# Precision_ATMega32U4.net
KiCad netlist of a schematic drawn in EAGLE
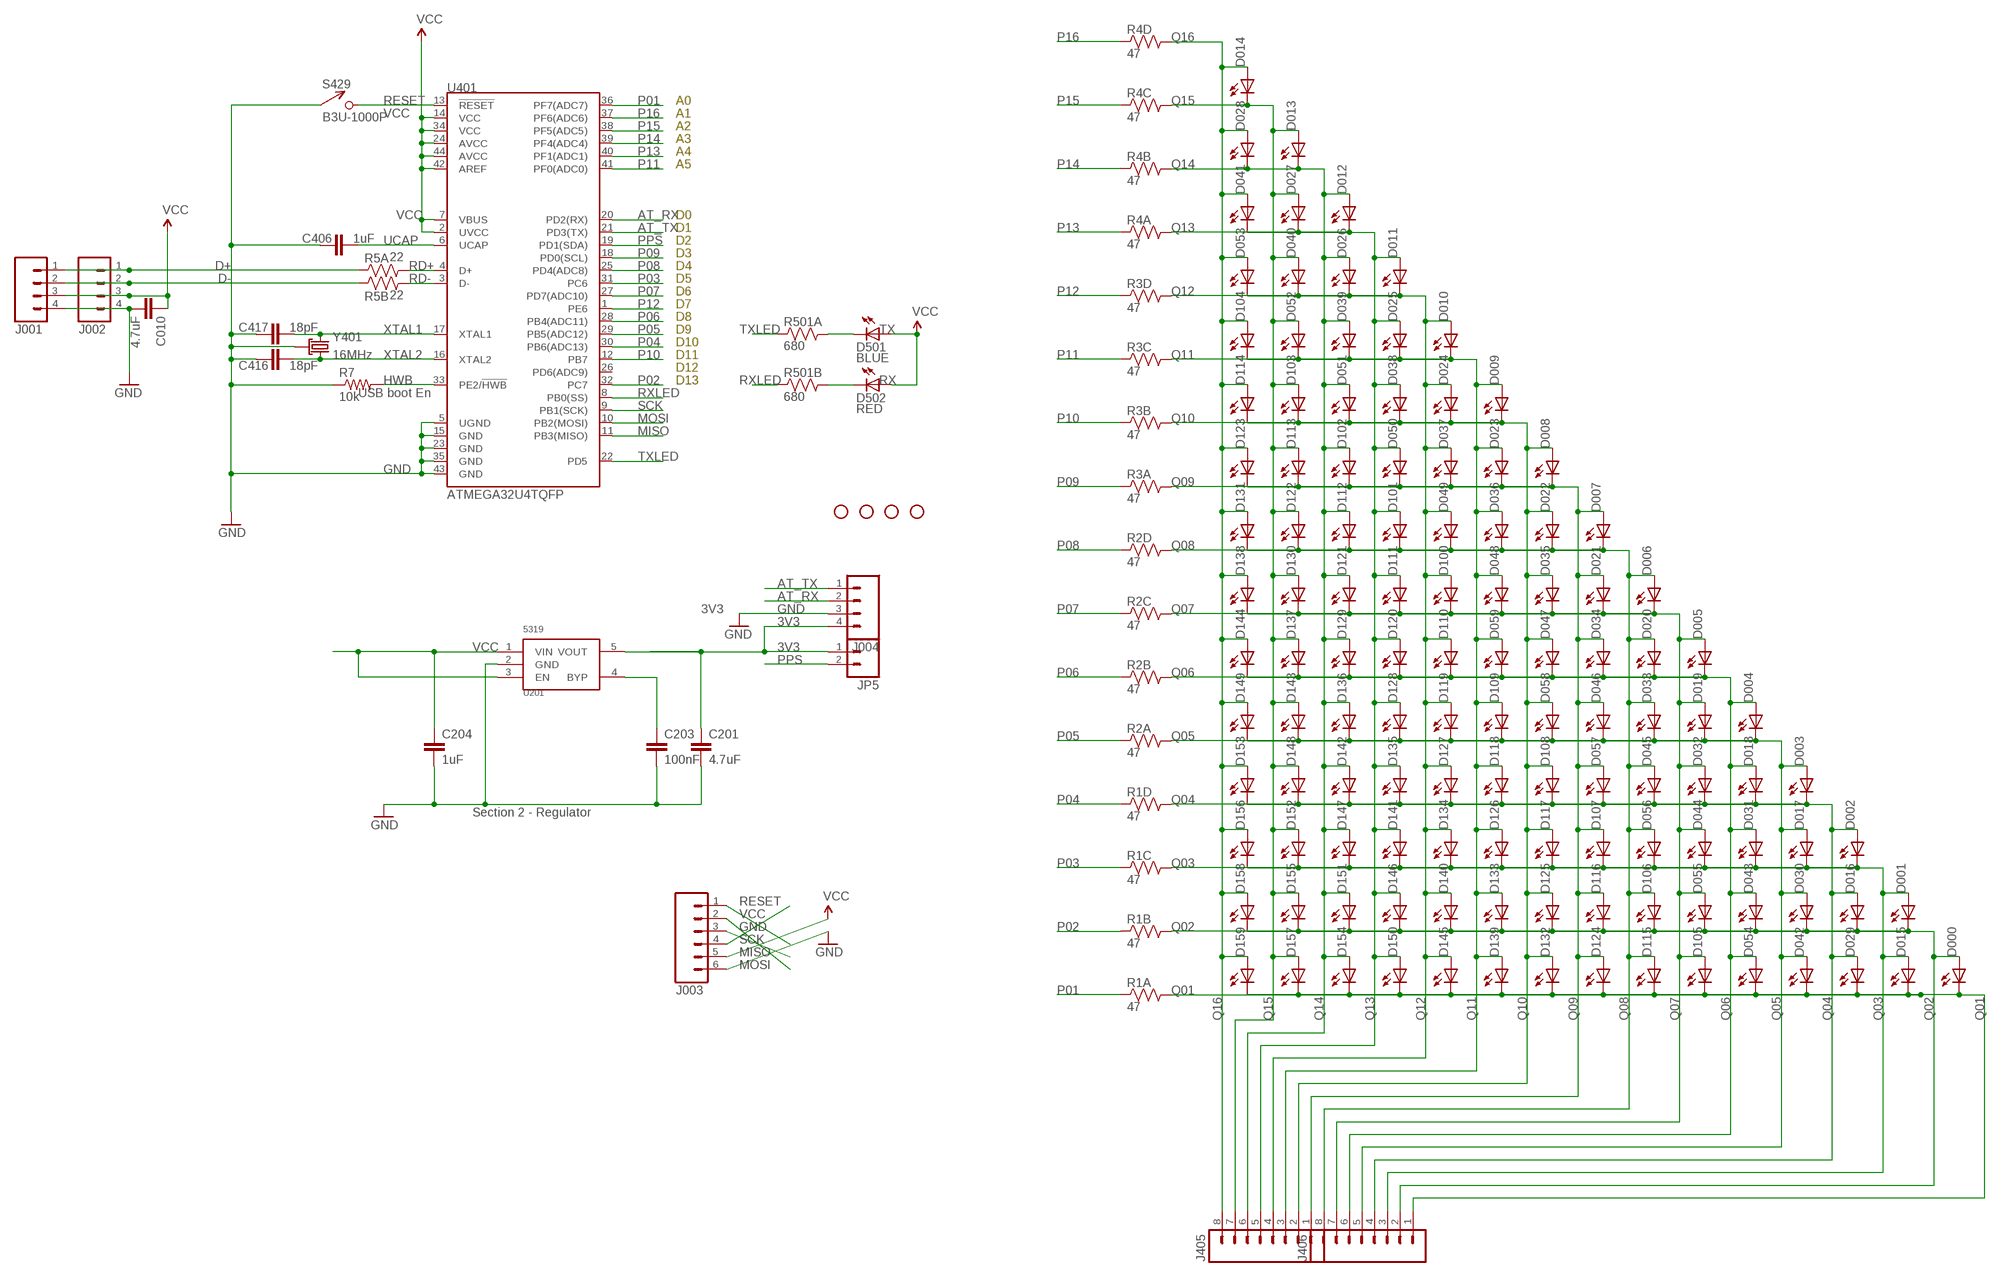
[diagram p0: schematic, sheet 1]

(export (version "E")
  (design (tool "Eeschema 10.0.6"))
  (components
    (comp (ref "C010")
      (value "4.7uF")
      (footprint "eagle-import:0603-CAP")
      (libsource (lib "eagle-import") (part "CAP0603-CAP"))
    )
    (comp (ref "C201")
      (value "4.7uF")
      (footprint "eagle-import:0402-CAP")
      (libsource (lib "eagle-import") (part "CAP0402-CAP"))
    )
    (comp (ref "C203")
      (value "100nF")
      (footprint "eagle-import:0402-CAP")
      (libsource (lib "eagle-import") (part "CAP0402-CAP"))
    )
    (comp (ref "C204")
      (value "1uF")
      (footprint "eagle-import:0402-CAP")
      (libsource (lib "eagle-import") (part "CAP0402-CAP"))
    )
    (comp (ref "C406")
      (value "1uF")
      (footprint "eagle-import:0603-CAP")
      (libsource (lib "eagle-import") (part "CAP0603-CAP"))
    )
    (comp (ref "C416")
      (value "18pF")
      (footprint "eagle-import:0603-CAP")
      (libsource (lib "eagle-import") (part "CAP0603-CAP"))
    )
    (comp (ref "C417")
      (value "18pF")
      (footprint "eagle-import:0603-CAP")
      (libsource (lib "eagle-import") (part "CAP0603-CAP"))
    )
    (comp (ref "D000")
      (value "HOUR")
      (footprint "eagle-import:LED-0603")
      (libsource (lib "eagle-import") (part "LED0603"))
    )
    (comp (ref "D001")
      (value "HOUR")
      (footprint "eagle-import:LED-0603")
      (libsource (lib "eagle-import") (part "LED0603"))
    )
    (comp (ref "D002")
      (value "HOUR")
      (footprint "eagle-import:LED-0603")
      (libsource (lib "eagle-import") (part "LED0603"))
    )
    (comp (ref "D003")
      (value "HOUR")
      (footprint "eagle-import:LED-0603")
      (libsource (lib "eagle-import") (part "LED0603"))
    )
    (comp (ref "D004")
      (value "HOUR")
      (footprint "eagle-import:LED-0603")
      (libsource (lib "eagle-import") (part "LED0603"))
    )
    (comp (ref "D005")
      (value "HOUR")
      (footprint "eagle-import:LED-0603")
      (libsource (lib "eagle-import") (part "LED0603"))
    )
    (comp (ref "D006")
      (value "HOUR")
      (footprint "eagle-import:LED-0603")
      (libsource (lib "eagle-import") (part "LED0603"))
    )
    (comp (ref "D007")
      (value "HOUR")
      (footprint "eagle-import:LED-0603")
      (libsource (lib "eagle-import") (part "LED0603"))
    )
    (comp (ref "D008")
      (value "HOUR")
      (footprint "eagle-import:LED-0603")
      (libsource (lib "eagle-import") (part "LED0603"))
    )
    (comp (ref "D009")
      (value "HOUR")
      (footprint "eagle-import:LED-0603")
      (libsource (lib "eagle-import") (part "LED0603"))
    )
    (comp (ref "D010")
      (value "HOUR")
      (footprint "eagle-import:LED-0603")
      (libsource (lib "eagle-import") (part "LED0603"))
    )
    (comp (ref "D011")
      (value "HOUR")
      (footprint "eagle-import:LED-0603")
      (libsource (lib "eagle-import") (part "LED0603"))
    )
    (comp (ref "D012")
      (value "HOUR")
      (footprint "eagle-import:LED-0603")
      (libsource (lib "eagle-import") (part "LED0603"))
    )
    (comp (ref "D013")
      (value "HOUR")
      (footprint "eagle-import:LED-0603")
      (libsource (lib "eagle-import") (part "LED0603"))
    )
    (comp (ref "D014")
      (value "HOUR")
      (footprint "eagle-import:LED-0603")
      (libsource (lib "eagle-import") (part "LED0603"))
    )
    (comp (ref "D015")
      (value "HOUR")
      (footprint "eagle-import:LED-0603")
      (libsource (lib "eagle-import") (part "LED0603"))
    )
    (comp (ref "D016")
      (value "HOUR")
      (footprint "eagle-import:LED-0603")
      (libsource (lib "eagle-import") (part "LED0603"))
    )
    (comp (ref "D017")
      (value "HOUR")
      (footprint "eagle-import:LED-0603")
      (libsource (lib "eagle-import") (part "LED0603"))
    )
    (comp (ref "D018")
      (value "HOUR")
      (footprint "eagle-import:LED-0603")
      (libsource (lib "eagle-import") (part "LED0603"))
    )
    (comp (ref "D019")
      (value "HOUR")
      (footprint "eagle-import:LED-0603")
      (libsource (lib "eagle-import") (part "LED0603"))
    )
    (comp (ref "D020")
      (value "HOUR")
      (footprint "eagle-import:LED-0603")
      (libsource (lib "eagle-import") (part "LED0603"))
    )
    (comp (ref "D021")
      (value "HOUR")
      (footprint "eagle-import:LED-0603")
      (libsource (lib "eagle-import") (part "LED0603"))
    )
    (comp (ref "D022")
      (value "HOUR")
      (footprint "eagle-import:LED-0603")
      (libsource (lib "eagle-import") (part "LED0603"))
    )
    (comp (ref "D023")
      (value "HOUR")
      (footprint "eagle-import:LED-0603")
      (libsource (lib "eagle-import") (part "LED0603"))
    )
    (comp (ref "D024")
      (value "HOUR")
      (footprint "eagle-import:LED-0603")
      (libsource (lib "eagle-import") (part "LED0603"))
    )
    (comp (ref "D025")
      (value "HOUR")
      (footprint "eagle-import:LED-0603")
      (libsource (lib "eagle-import") (part "LED0603"))
    )
    (comp (ref "D026")
      (value "HOUR")
      (footprint "eagle-import:LED-0603")
      (libsource (lib "eagle-import") (part "LED0603"))
    )
    (comp (ref "D027")
      (value "HOUR")
      (footprint "eagle-import:LED-0603")
      (libsource (lib "eagle-import") (part "LED0603"))
    )
    (comp (ref "D028")
      (value "HOUR")
      (footprint "eagle-import:LED-0603")
      (libsource (lib "eagle-import") (part "LED0603"))
    )
    (comp (ref "D029")
      (value "HOUR")
      (footprint "eagle-import:LED-0603")
      (libsource (lib "eagle-import") (part "LED0603"))
    )
    (comp (ref "D030")
      (value "HOUR")
      (footprint "eagle-import:LED-0603")
      (libsource (lib "eagle-import") (part "LED0603"))
    )
    (comp (ref "D031")
      (value "HOUR")
      (footprint "eagle-import:LED-0603")
      (libsource (lib "eagle-import") (part "LED0603"))
    )
    (comp (ref "D032")
      (value "HOUR")
      (footprint "eagle-import:LED-0603")
      (libsource (lib "eagle-import") (part "LED0603"))
    )
    (comp (ref "D033")
      (value "HOUR")
      (footprint "eagle-import:LED-0603")
      (libsource (lib "eagle-import") (part "LED0603"))
    )
    (comp (ref "D034")
      (value "HOUR")
      (footprint "eagle-import:LED-0603")
      (libsource (lib "eagle-import") (part "LED0603"))
    )
    (comp (ref "D035")
      (value "HOUR")
      (footprint "eagle-import:LED-0603")
      (libsource (lib "eagle-import") (part "LED0603"))
    )
    (comp (ref "D036")
      (value "HOUR")
      (footprint "eagle-import:LED-0603")
      (libsource (lib "eagle-import") (part "LED0603"))
    )
    (comp (ref "D037")
      (value "HOUR")
      (footprint "eagle-import:LED-0603")
      (libsource (lib "eagle-import") (part "LED0603"))
    )
    (comp (ref "D038")
      (value "HOUR")
      (footprint "eagle-import:LED-0603")
      (libsource (lib "eagle-import") (part "LED0603"))
    )
    (comp (ref "D039")
      (value "HOUR")
      (footprint "eagle-import:LED-0603")
      (libsource (lib "eagle-import") (part "LED0603"))
    )
    (comp (ref "D040")
      (value "HOUR")
      (footprint "eagle-import:LED-0603")
      (libsource (lib "eagle-import") (part "LED0603"))
    )
    (comp (ref "D041")
      (value "HOUR")
      (footprint "eagle-import:LED-0603")
      (libsource (lib "eagle-import") (part "LED0603"))
    )
    (comp (ref "D042")
      (value "HOUR")
      (footprint "eagle-import:LED-0603")
      (libsource (lib "eagle-import") (part "LED0603"))
    )
    (comp (ref "D043")
      (value "HOUR")
      (footprint "eagle-import:LED-0603")
      (libsource (lib "eagle-import") (part "LED0603"))
    )
    (comp (ref "D044")
      (value "HOUR")
      (footprint "eagle-import:LED-0603")
      (libsource (lib "eagle-import") (part "LED0603"))
    )
    (comp (ref "D045")
      (value "HOUR")
      (footprint "eagle-import:LED-0603")
      (libsource (lib "eagle-import") (part "LED0603"))
    )
    (comp (ref "D046")
      (value "HOUR")
      (footprint "eagle-import:LED-0603")
      (libsource (lib "eagle-import") (part "LED0603"))
    )
    (comp (ref "D047")
      (value "HOUR")
      (footprint "eagle-import:LED-0603")
      (libsource (lib "eagle-import") (part "LED0603"))
    )
    (comp (ref "D048")
      (value "HOUR")
      (footprint "eagle-import:LED-0603")
      (libsource (lib "eagle-import") (part "LED0603"))
    )
    (comp (ref "D049")
      (value "HOUR")
      (footprint "eagle-import:LED-0603")
      (libsource (lib "eagle-import") (part "LED0603"))
    )
    (comp (ref "D050")
      (value "HOUR")
      (footprint "eagle-import:LED-0603")
      (libsource (lib "eagle-import") (part "LED0603"))
    )
    (comp (ref "D051")
      (value "HOUR")
      (footprint "eagle-import:LED-0603")
      (libsource (lib "eagle-import") (part "LED0603"))
    )
    (comp (ref "D052")
      (value "HOUR")
      (footprint "eagle-import:LED-0603")
      (libsource (lib "eagle-import") (part "LED0603"))
    )
    (comp (ref "D053")
      (value "HOUR")
      (footprint "eagle-import:LED-0603")
      (libsource (lib "eagle-import") (part "LED0603"))
    )
    (comp (ref "D054")
      (value "HOUR")
      (footprint "eagle-import:LED-0603")
      (libsource (lib "eagle-import") (part "LED0603"))
    )
    (comp (ref "D055")
      (value "HOUR")
      (footprint "eagle-import:LED-0603")
      (libsource (lib "eagle-import") (part "LED0603"))
    )
    (comp (ref "D056")
      (value "HOUR")
      (footprint "eagle-import:LED-0603")
      (libsource (lib "eagle-import") (part "LED0603"))
    )
    (comp (ref "D057")
      (value "HOUR")
      (footprint "eagle-import:LED-0603")
      (libsource (lib "eagle-import") (part "LED0603"))
    )
    (comp (ref "D058")
      (value "HOUR")
      (footprint "eagle-import:LED-0603")
      (libsource (lib "eagle-import") (part "LED0603"))
    )
    (comp (ref "D059")
      (value "HOUR")
      (footprint "eagle-import:LED-0603")
      (libsource (lib "eagle-import") (part "LED0603"))
    )
    (comp (ref "D100")
      (value "HOUR")
      (footprint "eagle-import:LED-0603")
      (libsource (lib "eagle-import") (part "LED0603"))
    )
    (comp (ref "D101")
      (value "HOUR")
      (footprint "eagle-import:LED-0603")
      (libsource (lib "eagle-import") (part "LED0603"))
    )
    (comp (ref "D102")
      (value "HOUR")
      (footprint "eagle-import:LED-0603")
      (libsource (lib "eagle-import") (part "LED0603"))
    )
    (comp (ref "D103")
      (value "HOUR")
      (footprint "eagle-import:LED-0603")
      (libsource (lib "eagle-import") (part "LED0603"))
    )
    (comp (ref "D104")
      (value "HOUR")
      (footprint "eagle-import:LED-0603")
      (libsource (lib "eagle-import") (part "LED0603"))
    )
    (comp (ref "D105")
      (value "HOUR")
      (footprint "eagle-import:LED-0603")
      (libsource (lib "eagle-import") (part "LED0603"))
    )
    (comp (ref "D106")
      (value "HOUR")
      (footprint "eagle-import:LED-0603")
      (libsource (lib "eagle-import") (part "LED0603"))
    )
    (comp (ref "D107")
      (value "HOUR")
      (footprint "eagle-import:LED-0603")
      (libsource (lib "eagle-import") (part "LED0603"))
    )
    (comp (ref "D108")
      (value "HOUR")
      (footprint "eagle-import:LED-0603")
      (libsource (lib "eagle-import") (part "LED0603"))
    )
    (comp (ref "D109")
      (value "HOUR")
      (footprint "eagle-import:LED-0603")
      (libsource (lib "eagle-import") (part "LED0603"))
    )
    (comp (ref "D110")
      (value "HOUR")
      (footprint "eagle-import:LED-0603")
      (libsource (lib "eagle-import") (part "LED0603"))
    )
    (comp (ref "D111")
      (value "HOUR")
      (footprint "eagle-import:LED-0603")
      (libsource (lib "eagle-import") (part "LED0603"))
    )
    (comp (ref "D112")
      (value "HOUR")
      (footprint "eagle-import:LED-0603")
      (libsource (lib "eagle-import") (part "LED0603"))
    )
    (comp (ref "D113")
      (value "HOUR")
      (footprint "eagle-import:LED-0603")
      (libsource (lib "eagle-import") (part "LED0603"))
    )
    (comp (ref "D114")
      (value "HOUR")
      (footprint "eagle-import:LED-0603")
      (libsource (lib "eagle-import") (part "LED0603"))
    )
    (comp (ref "D115")
      (value "HOUR")
      (footprint "eagle-import:LED-0603")
      (libsource (lib "eagle-import") (part "LED0603"))
    )
    (comp (ref "D116")
      (value "HOUR")
      (footprint "eagle-import:LED-0603")
      (libsource (lib "eagle-import") (part "LED0603"))
    )
    (comp (ref "D117")
      (value "HOUR")
      (footprint "eagle-import:LED-0603")
      (libsource (lib "eagle-import") (part "LED0603"))
    )
    (comp (ref "D118")
      (value "HOUR")
      (footprint "eagle-import:LED-0603")
      (libsource (lib "eagle-import") (part "LED0603"))
    )
    (comp (ref "D119")
      (value "HOUR")
      (footprint "eagle-import:LED-0603")
      (libsource (lib "eagle-import") (part "LED0603"))
    )
    (comp (ref "D120")
      (value "HOUR")
      (footprint "eagle-import:LED-0603")
      (libsource (lib "eagle-import") (part "LED0603"))
    )
    (comp (ref "D121")
      (value "HOUR")
      (footprint "eagle-import:LED-0603")
      (libsource (lib "eagle-import") (part "LED0603"))
    )
    (comp (ref "D122")
      (value "HOUR")
      (footprint "eagle-import:LED-0603")
      (libsource (lib "eagle-import") (part "LED0603"))
    )
    (comp (ref "D123")
      (value "HOUR")
      (footprint "eagle-import:LED-0603")
      (libsource (lib "eagle-import") (part "LED0603"))
    )
    (comp (ref "D124")
      (value "HOUR")
      (footprint "eagle-import:LED-0603")
      (libsource (lib "eagle-import") (part "LED0603"))
    )
    (comp (ref "D125")
      (value "HOUR")
      (footprint "eagle-import:LED-0603")
      (libsource (lib "eagle-import") (part "LED0603"))
    )
    (comp (ref "D126")
      (value "HOUR")
      (footprint "eagle-import:LED-0603")
      (libsource (lib "eagle-import") (part "LED0603"))
    )
    (comp (ref "D127")
      (value "HOUR")
      (footprint "eagle-import:LED-0603")
      (libsource (lib "eagle-import") (part "LED0603"))
    )
    (comp (ref "D128")
      (value "HOUR")
      (footprint "eagle-import:LED-0603")
      (libsource (lib "eagle-import") (part "LED0603"))
    )
    (comp (ref "D129")
      (value "HOUR")
      (footprint "eagle-import:LED-0603")
      (libsource (lib "eagle-import") (part "LED0603"))
    )
    (comp (ref "D130")
      (value "HOUR")
      (footprint "eagle-import:LED-0603")
      (libsource (lib "eagle-import") (part "LED0603"))
    )
    (comp (ref "D131")
      (value "HOUR")
      (footprint "eagle-import:LED-0603")
      (libsource (lib "eagle-import") (part "LED0603"))
    )
    (comp (ref "D132")
      (value "HOUR")
      (footprint "eagle-import:LED-0603")
      (libsource (lib "eagle-import") (part "LED0603"))
    )
    (comp (ref "D133")
      (value "HOUR")
      (footprint "eagle-import:LED-0603")
      (libsource (lib "eagle-import") (part "LED0603"))
    )
    (comp (ref "D134")
      (value "HOUR")
      (footprint "eagle-import:LED-0603")
      (libsource (lib "eagle-import") (part "LED0603"))
    )
    (comp (ref "D135")
      (value "HOUR")
      (footprint "eagle-import:LED-0603")
      (libsource (lib "eagle-import") (part "LED0603"))
    )
    (comp (ref "D136")
      (value "HOUR")
      (footprint "eagle-import:LED-0603")
      (libsource (lib "eagle-import") (part "LED0603"))
    )
    (comp (ref "D137")
      (value "HOUR")
      (footprint "eagle-import:LED-0603")
      (libsource (lib "eagle-import") (part "LED0603"))
    )
    (comp (ref "D138")
      (value "HOUR")
      (footprint "eagle-import:LED-0603")
      (libsource (lib "eagle-import") (part "LED0603"))
    )
    (comp (ref "D139")
      (value "HOUR")
      (footprint "eagle-import:LED-0603")
      (libsource (lib "eagle-import") (part "LED0603"))
    )
    (comp (ref "D140")
      (value "HOUR")
      (footprint "eagle-import:LED-0603")
      (libsource (lib "eagle-import") (part "LED0603"))
    )
    (comp (ref "D141")
      (value "HOUR")
      (footprint "eagle-import:LED-0603")
      (libsource (lib "eagle-import") (part "LED0603"))
    )
    (comp (ref "D142")
      (value "HOUR")
      (footprint "eagle-import:LED-0603")
      (libsource (lib "eagle-import") (part "LED0603"))
    )
    (comp (ref "D143")
      (value "HOUR")
      (footprint "eagle-import:LED-0603")
      (libsource (lib "eagle-import") (part "LED0603"))
    )
    (comp (ref "D144")
      (value "HOUR")
      (footprint "eagle-import:LED-0603")
      (libsource (lib "eagle-import") (part "LED0603"))
    )
    (comp (ref "D145")
      (value "HOUR")
      (footprint "eagle-import:LED-0603")
      (libsource (lib "eagle-import") (part "LED0603"))
    )
    (comp (ref "D146")
      (value "HOUR")
      (footprint "eagle-import:LED-0603")
      (libsource (lib "eagle-import") (part "LED0603"))
    )
    (comp (ref "D147")
      (value "HOUR")
      (footprint "eagle-import:LED-0603")
      (libsource (lib "eagle-import") (part "LED0603"))
    )
    (comp (ref "D148")
      (value "HOUR")
      (footprint "eagle-import:LED-0603")
      (libsource (lib "eagle-import") (part "LED0603"))
    )
    (comp (ref "D149")
      (value "HOUR")
      (footprint "eagle-import:LED-0603")
      (libsource (lib "eagle-import") (part "LED0603"))
    )
    (comp (ref "D150")
      (value "HOUR")
      (footprint "eagle-import:LED-0603")
      (libsource (lib "eagle-import") (part "LED0603"))
    )
    (comp (ref "D151")
      (value "HOUR")
      (footprint "eagle-import:LED-0603")
      (libsource (lib "eagle-import") (part "LED0603"))
    )
    (comp (ref "D152")
      (value "HOUR")
      (footprint "eagle-import:LED-0603")
      (libsource (lib "eagle-import") (part "LED0603"))
    )
    (comp (ref "D153")
      (value "HOUR")
      (footprint "eagle-import:LED-0603")
      (libsource (lib "eagle-import") (part "LED0603"))
    )
    (comp (ref "D154")
      (value "HOUR")
      (footprint "eagle-import:LED-0603")
      (libsource (lib "eagle-import") (part "LED0603"))
    )
    (comp (ref "D155")
      (value "HOUR")
      (footprint "eagle-import:LED-0603")
      (libsource (lib "eagle-import") (part "LED0603"))
    )
    (comp (ref "D156")
      (value "HOUR")
      (footprint "eagle-import:LED-0603")
      (libsource (lib "eagle-import") (part "LED0603"))
    )
    (comp (ref "D157")
      (value "HOUR")
      (footprint "eagle-import:LED-0603")
      (libsource (lib "eagle-import") (part "LED0603"))
    )
    (comp (ref "D158")
      (value "HOUR")
      (footprint "eagle-import:LED-0603")
      (libsource (lib "eagle-import") (part "LED0603"))
    )
    (comp (ref "D159")
      (value "HOUR")
      (footprint "eagle-import:LED-0603")
      (libsource (lib "eagle-import") (part "LED0603"))
    )
    (comp (ref "D501")
      (value "BLUE")
      (footprint "eagle-import:LED-0603")
      (libsource (lib "eagle-import") (part "LED0603"))
    )
    (comp (ref "D502")
      (value "RED")
      (footprint "eagle-import:LED-0603")
      (libsource (lib "eagle-import") (part "LED0603"))
    )
    (comp (ref "J001")
      (value "M04PTH")
      (footprint "eagle-import:1X04")
      (libsource (lib "eagle-import") (part "M04PTH"))
    )
    (comp (ref "J002")
      (value "M04PTH")
      (footprint "eagle-import:1X04")
      (libsource (lib "eagle-import") (part "M04PTH"))
    )
    (comp (ref "J003")
      (value "M06SIP")
      (footprint "eagle-import:1X06")
      (libsource (lib "eagle-import") (part "M06SIP"))
    )
    (comp (ref "J004")
      (value "M04PTH")
      (footprint "eagle-import:1X04")
      (libsource (lib "eagle-import") (part "M04PTH"))
    )
    (comp (ref "J405")
      (value "M081X08")
      (footprint "eagle-import:1X08")
      (libsource (lib "eagle-import") (part "M081X08"))
    )
    (comp (ref "J406")
      (value "M081X08")
      (footprint "eagle-import:1X08")
      (libsource (lib "eagle-import") (part "M081X08"))
    )
    (comp (ref "JP1")
      (value "STAND-OFF")
      (footprint "eagle-import:STAND-OFF")
      (libsource (lib "eagle-import") (part "STAND-OFF"))
    )
    (comp (ref "JP2")
      (value "STAND-OFF")
      (footprint "eagle-import:STAND-OFF")
      (libsource (lib "eagle-import") (part "STAND-OFF"))
    )
    (comp (ref "JP3")
      (value "STAND-OFF")
      (footprint "eagle-import:STAND-OFF")
      (libsource (lib "eagle-import") (part "STAND-OFF"))
    )
    (comp (ref "JP4")
      (value "STAND-OFF")
      (footprint "eagle-import:STAND-OFF")
      (libsource (lib "eagle-import") (part "STAND-OFF"))
    )
    (comp (ref "JP5")
      (value "M02PTH")
      (footprint "eagle-import:1X02")
      (libsource (lib "eagle-import") (part "M02PTH"))
    )
    (comp (ref "R1")
      (value "47")
      (footprint "eagle-import:CRA04")
      (libsource (lib "eagle-import") (part "RP404"))
    )
    (comp (ref "R2")
      (value "47")
      (footprint "eagle-import:CRA04")
      (libsource (lib "eagle-import") (part "RP404"))
    )
    (comp (ref "R3")
      (value "47")
      (footprint "eagle-import:CRA04")
      (libsource (lib "eagle-import") (part "RP404"))
    )
    (comp (ref "R4")
      (value "47")
      (footprint "eagle-import:CRA04")
      (libsource (lib "eagle-import") (part "RP404"))
    )
    (comp (ref "R5")
      (value "22")
      (footprint "eagle-import:CRA02")
      (libsource (lib "eagle-import") (part "RP2EXB24V"))
    )
    (comp (ref "R7")
      (value "10k")
      (footprint "eagle-import:0603-RES")
      (libsource (lib "eagle-import") (part "RESISTOR0603-RES"))
    )
    (comp (ref "R501")
      (value "680")
      (footprint "eagle-import:CRA02")
      (libsource (lib "eagle-import") (part "RP2EXB24V"))
    )
    (comp (ref "S429")
      (value "B3U-1000P")
      (footprint "eagle-import:B3U-1000P")
      (libsource (lib "eagle-import") (part "B3U-1000P"))
    )
    (comp (ref "U201")
      (value "5319")
      (footprint "eagle-import:SOT-23-5")
      (libsource (lib "eagle-import") (part "MIC5319D5"))
    )
    (comp (ref "U401")
      (value "ATMEGA32U4TQFP")
      (footprint "eagle-import:SPARKFUN-DIGITALIC_TQFP44")
      (libsource (lib "eagle-import") (part "ATMEGA32U4TQFP"))
    )
    (comp (ref "Y401")
      (value "16MHz")
      (footprint "eagle-import:CRYSTAL_SMD")
      (libsource (lib "eagle-import") (part "TSX-3225"))
    )
  )
  (nets
    (net (code "1") (name "/3V3") (class "Default")
      (node (ref "C201") (pin "1") (pinfunction "1_1") (pintype "passive"))
      (node (ref "J004") (pin "4") (pinfunction "4_4") (pintype "passive"))
      (node (ref "JP5") (pin "1") (pinfunction "1_1") (pintype "passive"))
      (node (ref "U201") (pin "5") (pinfunction "VOUT_5") (pintype "bidirectional"))
    )
    (net (code "2") (name "/AT_RX") (class "Default")
      (node (ref "J004") (pin "2") (pinfunction "2_2") (pintype "passive"))
      (node (ref "U401") (pin "20") (pinfunction "PD2(RX)_20") (pintype "bidirectional"))
    )
    (net (code "3") (name "/AT_TX") (class "Default")
      (node (ref "J004") (pin "1") (pinfunction "1_1") (pintype "passive"))
      (node (ref "U401") (pin "21") (pinfunction "PD3(TX)_21") (pintype "bidirectional"))
    )
    (net (code "4") (name "/D+") (class "Default")
      (node (ref "J001") (pin "1") (pinfunction "1_1") (pintype "passive"))
      (node (ref "J002") (pin "1") (pinfunction "1_1") (pintype "passive"))
      (node (ref "R5") (pin "1") (pinfunction "1_1") (pintype "passive"))
    )
    (net (code "5") (name "/D-") (class "Default")
      (node (ref "J001") (pin "2") (pinfunction "2_2") (pintype "passive"))
      (node (ref "J002") (pin "2") (pinfunction "2_2") (pintype "passive"))
      (node (ref "R5") (pin "2") (pinfunction "1_2") (pintype "passive"))
    )
    (net (code "6") (name "/HWB") (class "Default")
      (node (ref "R7") (pin "2") (pinfunction "2_2") (pintype "passive"))
      (node (ref "U401") (pin "33") (pinfunction "PE2/~{HWB}_33") (pintype "bidirectional"))
    )
    (net (code "7") (name "/MISO") (class "Default")
      (node (ref "J003") (pin "3") (pinfunction "3_3") (pintype "passive"))
      (node (ref "U401") (pin "11") (pinfunction "PB3(MISO)_11") (pintype "bidirectional"))
    )
    (net (code "8") (name "/MOSI") (class "Default")
      (node (ref "J003") (pin "2") (pinfunction "2_2") (pintype "passive"))
      (node (ref "U401") (pin "10") (pinfunction "PB2(MOSI)_10") (pintype "bidirectional"))
    )
    (net (code "9") (name "/P01") (class "Default")
      (node (ref "R1") (pin "1") (pinfunction "1_1") (pintype "passive"))
      (node (ref "U401") (pin "36") (pinfunction "PF7(ADC7)_36") (pintype "bidirectional"))
    )
    (net (code "10") (name "/P02") (class "Default")
      (node (ref "R1") (pin "2") (pinfunction "1_2") (pintype "passive"))
      (node (ref "U401") (pin "32") (pinfunction "PC7_32") (pintype "bidirectional"))
    )
    (net (code "11") (name "/P03") (class "Default")
      (node (ref "R1") (pin "3") (pinfunction "1_3") (pintype "passive"))
      (node (ref "U401") (pin "31") (pinfunction "PC6_31") (pintype "bidirectional"))
    )
    (net (code "12") (name "/P04") (class "Default")
      (node (ref "R1") (pin "4") (pinfunction "1_4") (pintype "passive"))
      (node (ref "U401") (pin "30") (pinfunction "PB6(ADC13)_30") (pintype "bidirectional"))
    )
    (net (code "13") (name "/P05") (class "Default")
      (node (ref "R2") (pin "1") (pinfunction "1_1") (pintype "passive"))
      (node (ref "U401") (pin "29") (pinfunction "PB5(ADC12)_29") (pintype "bidirectional"))
    )
    (net (code "14") (name "/P06") (class "Default")
      (node (ref "R2") (pin "2") (pinfunction "1_2") (pintype "passive"))
      (node (ref "U401") (pin "28") (pinfunction "PB4(ADC11)_28") (pintype "bidirectional"))
    )
    (net (code "15") (name "/P07") (class "Default")
      (node (ref "R2") (pin "3") (pinfunction "1_3") (pintype "passive"))
      (node (ref "U401") (pin "27") (pinfunction "PD7(ADC10)_27") (pintype "bidirectional"))
    )
    (net (code "16") (name "/P08") (class "Default")
      (node (ref "R2") (pin "4") (pinfunction "1_4") (pintype "passive"))
      (node (ref "U401") (pin "25") (pinfunction "PD4(ADC8)_25") (pintype "bidirectional"))
    )
    (net (code "17") (name "/P09") (class "Default")
      (node (ref "R3") (pin "1") (pinfunction "1_1") (pintype "passive"))
      (node (ref "U401") (pin "18") (pinfunction "PD0(SCL)_18") (pintype "bidirectional"))
    )
    (net (code "18") (name "/P10") (class "Default")
      (node (ref "R3") (pin "2") (pinfunction "1_2") (pintype "passive"))
      (node (ref "U401") (pin "12") (pinfunction "PB7_12") (pintype "bidirectional"))
    )
    (net (code "19") (name "/P11") (class "Default")
      (node (ref "R3") (pin "3") (pinfunction "1_3") (pintype "passive"))
      (node (ref "U401") (pin "41") (pinfunction "PF0(ADC0)_41") (pintype "bidirectional"))
    )
    (net (code "20") (name "/P12") (class "Default")
      (node (ref "R3") (pin "4") (pinfunction "1_4") (pintype "passive"))
      (node (ref "U401") (pin "1") (pinfunction "PE6_1") (pintype "bidirectional"))
    )
    (net (code "21") (name "/P13") (class "Default")
      (node (ref "R4") (pin "1") (pinfunction "1_1") (pintype "passive"))
      (node (ref "U401") (pin "40") (pinfunction "PF1(ADC1)_40") (pintype "bidirectional"))
    )
    (net (code "22") (name "/P14") (class "Default")
      (node (ref "R4") (pin "2") (pinfunction "1_2") (pintype "passive"))
      (node (ref "U401") (pin "39") (pinfunction "PF4(ADC4)_39") (pintype "bidirectional"))
    )
    (net (code "23") (name "/P15") (class "Default")
      (node (ref "R4") (pin "3") (pinfunction "1_3") (pintype "passive"))
      (node (ref "U401") (pin "38") (pinfunction "PF5(ADC5)_38") (pintype "bidirectional"))
    )
    (net (code "24") (name "/P16") (class "Default")
      (node (ref "R4") (pin "4") (pinfunction "1_4") (pintype "passive"))
      (node (ref "U401") (pin "37") (pinfunction "PF6(ADC6)_37") (pintype "bidirectional"))
    )
    (net (code "25") (name "/PPS") (class "Default")
      (node (ref "JP5") (pin "2") (pinfunction "2_2") (pintype "passive"))
      (node (ref "U401") (pin "19") (pinfunction "PD1(SDA)_19") (pintype "bidirectional"))
    )
    (net (code "26") (name "/Q01") (class "Default")
      (node (ref "D000") (pin "C") (pinfunction "C_C") (pintype "passive"))
      (node (ref "D015") (pin "C") (pinfunction "C_C") (pintype "passive"))
      (node (ref "D029") (pin "C") (pinfunction "C_C") (pintype "passive"))
      (node (ref "D042") (pin "C") (pinfunction "C_C") (pintype "passive"))
      (node (ref "D054") (pin "C") (pinfunction "C_C") (pintype "passive"))
      (node (ref "D105") (pin "C") (pinfunction "C_C") (pintype "passive"))
      (node (ref "D115") (pin "C") (pinfunction "C_C") (pintype "passive"))
      (node (ref "D124") (pin "C") (pinfunction "C_C") (pintype "passive"))
      (node (ref "D132") (pin "C") (pinfunction "C_C") (pintype "passive"))
      (node (ref "D139") (pin "C") (pinfunction "C_C") (pintype "passive"))
      (node (ref "D145") (pin "C") (pinfunction "C_C") (pintype "passive"))
      (node (ref "D150") (pin "C") (pinfunction "C_C") (pintype "passive"))
      (node (ref "D154") (pin "C") (pinfunction "C_C") (pintype "passive"))
      (node (ref "D157") (pin "C") (pinfunction "C_C") (pintype "passive"))
      (node (ref "D159") (pin "C") (pinfunction "C_C") (pintype "passive"))
      (node (ref "J406") (pin "1") (pinfunction "1_1") (pintype "passive"))
      (node (ref "R1") (pin "8") (pinfunction "2_8") (pintype "passive"))
    )
    (net (code "27") (name "/Q02") (class "Default")
      (node (ref "D000") (pin "A") (pinfunction "A_A") (pintype "passive"))
      (node (ref "D001") (pin "C") (pinfunction "C_C") (pintype "passive"))
      (node (ref "D016") (pin "C") (pinfunction "C_C") (pintype "passive"))
      (node (ref "D030") (pin "C") (pinfunction "C_C") (pintype "passive"))
      (node (ref "D043") (pin "C") (pinfunction "C_C") (pintype "passive"))
      (node (ref "D055") (pin "C") (pinfunction "C_C") (pintype "passive"))
      (node (ref "D106") (pin "C") (pinfunction "C_C") (pintype "passive"))
      (node (ref "D116") (pin "C") (pinfunction "C_C") (pintype "passive"))
      (node (ref "D125") (pin "C") (pinfunction "C_C") (pintype "passive"))
      (node (ref "D133") (pin "C") (pinfunction "C_C") (pintype "passive"))
      (node (ref "D140") (pin "C") (pinfunction "C_C") (pintype "passive"))
      (node (ref "D146") (pin "C") (pinfunction "C_C") (pintype "passive"))
      (node (ref "D151") (pin "C") (pinfunction "C_C") (pintype "passive"))
      (node (ref "D155") (pin "C") (pinfunction "C_C") (pintype "passive"))
      (node (ref "D158") (pin "C") (pinfunction "C_C") (pintype "passive"))
      (node (ref "J406") (pin "2") (pinfunction "2_2") (pintype "passive"))
      (node (ref "R1") (pin "7") (pinfunction "2_7") (pintype "passive"))
    )
    (net (code "28") (name "/Q03") (class "Default")
      (node (ref "D001") (pin "A") (pinfunction "A_A") (pintype "passive"))
      (node (ref "D002") (pin "C") (pinfunction "C_C") (pintype "passive"))
      (node (ref "D015") (pin "A") (pinfunction "A_A") (pintype "passive"))
      (node (ref "D017") (pin "C") (pinfunction "C_C") (pintype "passive"))
      (node (ref "D031") (pin "C") (pinfunction "C_C") (pintype "passive"))
      (node (ref "D044") (pin "C") (pinfunction "C_C") (pintype "passive"))
      (node (ref "D056") (pin "C") (pinfunction "C_C") (pintype "passive"))
      (node (ref "D107") (pin "C") (pinfunction "C_C") (pintype "passive"))
      (node (ref "D117") (pin "C") (pinfunction "C_C") (pintype "passive"))
      (node (ref "D126") (pin "C") (pinfunction "C_C") (pintype "passive"))
      (node (ref "D134") (pin "C") (pinfunction "C_C") (pintype "passive"))
      (node (ref "D141") (pin "C") (pinfunction "C_C") (pintype "passive"))
      (node (ref "D147") (pin "C") (pinfunction "C_C") (pintype "passive"))
      (node (ref "D152") (pin "C") (pinfunction "C_C") (pintype "passive"))
      (node (ref "D156") (pin "C") (pinfunction "C_C") (pintype "passive"))
      (node (ref "J406") (pin "3") (pinfunction "3_3") (pintype "passive"))
      (node (ref "R1") (pin "6") (pinfunction "2_6") (pintype "passive"))
    )
    (net (code "29") (name "/Q04") (class "Default")
      (node (ref "D002") (pin "A") (pinfunction "A_A") (pintype "passive"))
      (node (ref "D003") (pin "C") (pinfunction "C_C") (pintype "passive"))
      (node (ref "D016") (pin "A") (pinfunction "A_A") (pintype "passive"))
      (node (ref "D018") (pin "C") (pinfunction "C_C") (pintype "passive"))
      (node (ref "D029") (pin "A") (pinfunction "A_A") (pintype "passive"))
      (node (ref "D032") (pin "C") (pinfunction "C_C") (pintype "passive"))
      (node (ref "D045") (pin "C") (pinfunction "C_C") (pintype "passive"))
      (node (ref "D057") (pin "C") (pinfunction "C_C") (pintype "passive"))
      (node (ref "D108") (pin "C") (pinfunction "C_C") (pintype "passive"))
      (node (ref "D118") (pin "C") (pinfunction "C_C") (pintype "passive"))
      (node (ref "D127") (pin "C") (pinfunction "C_C") (pintype "passive"))
      (node (ref "D135") (pin "C") (pinfunction "C_C") (pintype "passive"))
      (node (ref "D142") (pin "C") (pinfunction "C_C") (pintype "passive"))
      (node (ref "D148") (pin "C") (pinfunction "C_C") (pintype "passive"))
      (node (ref "D153") (pin "C") (pinfunction "C_C") (pintype "passive"))
      (node (ref "J406") (pin "4") (pinfunction "4_4") (pintype "passive"))
      (node (ref "R1") (pin "5") (pinfunction "2_5") (pintype "passive"))
    )
    (net (code "30") (name "/Q05") (class "Default")
      (node (ref "D003") (pin "A") (pinfunction "A_A") (pintype "passive"))
      (node (ref "D004") (pin "C") (pinfunction "C_C") (pintype "passive"))
      (node (ref "D017") (pin "A") (pinfunction "A_A") (pintype "passive"))
      (node (ref "D019") (pin "C") (pinfunction "C_C") (pintype "passive"))
      (node (ref "D030") (pin "A") (pinfunction "A_A") (pintype "passive"))
      (node (ref "D033") (pin "C") (pinfunction "C_C") (pintype "passive"))
      (node (ref "D042") (pin "A") (pinfunction "A_A") (pintype "passive"))
      (node (ref "D046") (pin "C") (pinfunction "C_C") (pintype "passive"))
      (node (ref "D058") (pin "C") (pinfunction "C_C") (pintype "passive"))
      (node (ref "D109") (pin "C") (pinfunction "C_C") (pintype "passive"))
      (node (ref "D119") (pin "C") (pinfunction "C_C") (pintype "passive"))
      (node (ref "D128") (pin "C") (pinfunction "C_C") (pintype "passive"))
      (node (ref "D136") (pin "C") (pinfunction "C_C") (pintype "passive"))
      (node (ref "D143") (pin "C") (pinfunction "C_C") (pintype "passive"))
      (node (ref "D149") (pin "C") (pinfunction "C_C") (pintype "passive"))
      (node (ref "J406") (pin "5") (pinfunction "5_5") (pintype "passive"))
      (node (ref "R2") (pin "8") (pinfunction "2_8") (pintype "passive"))
    )
    (net (code "31") (name "/Q06") (class "Default")
      (node (ref "D004") (pin "A") (pinfunction "A_A") (pintype "passive"))
      (node (ref "D005") (pin "C") (pinfunction "C_C") (pintype "passive"))
      (node (ref "D018") (pin "A") (pinfunction "A_A") (pintype "passive"))
      (node (ref "D020") (pin "C") (pinfunction "C_C") (pintype "passive"))
      (node (ref "D031") (pin "A") (pinfunction "A_A") (pintype "passive"))
      (node (ref "D034") (pin "C") (pinfunction "C_C") (pintype "passive"))
      (node (ref "D043") (pin "A") (pinfunction "A_A") (pintype "passive"))
      (node (ref "D047") (pin "C") (pinfunction "C_C") (pintype "passive"))
      (node (ref "D054") (pin "A") (pinfunction "A_A") (pintype "passive"))
      (node (ref "D059") (pin "C") (pinfunction "C_C") (pintype "passive"))
      (node (ref "D110") (pin "C") (pinfunction "C_C") (pintype "passive"))
      (node (ref "D120") (pin "C") (pinfunction "C_C") (pintype "passive"))
      (node (ref "D129") (pin "C") (pinfunction "C_C") (pintype "passive"))
      (node (ref "D137") (pin "C") (pinfunction "C_C") (pintype "passive"))
      (node (ref "D144") (pin "C") (pinfunction "C_C") (pintype "passive"))
      (node (ref "J406") (pin "6") (pinfunction "6_6") (pintype "passive"))
      (node (ref "R2") (pin "7") (pinfunction "2_7") (pintype "passive"))
    )
    (net (code "32") (name "/Q07") (class "Default")
      (node (ref "D005") (pin "A") (pinfunction "A_A") (pintype "passive"))
      (node (ref "D006") (pin "C") (pinfunction "C_C") (pintype "passive"))
      (node (ref "D019") (pin "A") (pinfunction "A_A") (pintype "passive"))
      (node (ref "D021") (pin "C") (pinfunction "C_C") (pintype "passive"))
      (node (ref "D032") (pin "A") (pinfunction "A_A") (pintype "passive"))
      (node (ref "D035") (pin "C") (pinfunction "C_C") (pintype "passive"))
      (node (ref "D044") (pin "A") (pinfunction "A_A") (pintype "passive"))
      (node (ref "D048") (pin "C") (pinfunction "C_C") (pintype "passive"))
      (node (ref "D055") (pin "A") (pinfunction "A_A") (pintype "passive"))
      (node (ref "D100") (pin "C") (pinfunction "C_C") (pintype "passive"))
      (node (ref "D105") (pin "A") (pinfunction "A_A") (pintype "passive"))
      (node (ref "D111") (pin "C") (pinfunction "C_C") (pintype "passive"))
      (node (ref "D121") (pin "C") (pinfunction "C_C") (pintype "passive"))
      (node (ref "D130") (pin "C") (pinfunction "C_C") (pintype "passive"))
      (node (ref "D138") (pin "C") (pinfunction "C_C") (pintype "passive"))
      (node (ref "J406") (pin "7") (pinfunction "7_7") (pintype "passive"))
      (node (ref "R2") (pin "6") (pinfunction "2_6") (pintype "passive"))
    )
    (net (code "33") (name "/Q08") (class "Default")
      (node (ref "D006") (pin "A") (pinfunction "A_A") (pintype "passive"))
      (node (ref "D007") (pin "C") (pinfunction "C_C") (pintype "passive"))
      (node (ref "D020") (pin "A") (pinfunction "A_A") (pintype "passive"))
      (node (ref "D022") (pin "C") (pinfunction "C_C") (pintype "passive"))
      (node (ref "D033") (pin "A") (pinfunction "A_A") (pintype "passive"))
      (node (ref "D036") (pin "C") (pinfunction "C_C") (pintype "passive"))
      (node (ref "D045") (pin "A") (pinfunction "A_A") (pintype "passive"))
      (node (ref "D049") (pin "C") (pinfunction "C_C") (pintype "passive"))
      (node (ref "D056") (pin "A") (pinfunction "A_A") (pintype "passive"))
      (node (ref "D101") (pin "C") (pinfunction "C_C") (pintype "passive"))
      (node (ref "D106") (pin "A") (pinfunction "A_A") (pintype "passive"))
      (node (ref "D112") (pin "C") (pinfunction "C_C") (pintype "passive"))
      (node (ref "D115") (pin "A") (pinfunction "A_A") (pintype "passive"))
      (node (ref "D122") (pin "C") (pinfunction "C_C") (pintype "passive"))
      (node (ref "D131") (pin "C") (pinfunction "C_C") (pintype "passive"))
      (node (ref "J406") (pin "8") (pinfunction "8_8") (pintype "passive"))
      (node (ref "R2") (pin "5") (pinfunction "2_5") (pintype "passive"))
    )
    (net (code "34") (name "/Q09") (class "Default")
      (node (ref "D007") (pin "A") (pinfunction "A_A") (pintype "passive"))
      (node (ref "D008") (pin "C") (pinfunction "C_C") (pintype "passive"))
      (node (ref "D021") (pin "A") (pinfunction "A_A") (pintype "passive"))
      (node (ref "D023") (pin "C") (pinfunction "C_C") (pintype "passive"))
      (node (ref "D034") (pin "A") (pinfunction "A_A") (pintype "passive"))
      (node (ref "D037") (pin "C") (pinfunction "C_C") (pintype "passive"))
      (node (ref "D046") (pin "A") (pinfunction "A_A") (pintype "passive"))
      (node (ref "D050") (pin "C") (pinfunction "C_C") (pintype "passive"))
      (node (ref "D057") (pin "A") (pinfunction "A_A") (pintype "passive"))
      (node (ref "D102") (pin "C") (pinfunction "C_C") (pintype "passive"))
      (node (ref "D107") (pin "A") (pinfunction "A_A") (pintype "passive"))
      (node (ref "D113") (pin "C") (pinfunction "C_C") (pintype "passive"))
      (node (ref "D116") (pin "A") (pinfunction "A_A") (pintype "passive"))
      (node (ref "D123") (pin "C") (pinfunction "C_C") (pintype "passive"))
      (node (ref "D124") (pin "A") (pinfunction "A_A") (pintype "passive"))
      (node (ref "J405") (pin "1") (pinfunction "1_1") (pintype "passive"))
      (node (ref "R3") (pin "8") (pinfunction "2_8") (pintype "passive"))
    )
    (net (code "35") (name "/Q10") (class "Default")
      (node (ref "D008") (pin "A") (pinfunction "A_A") (pintype "passive"))
      (node (ref "D009") (pin "C") (pinfunction "C_C") (pintype "passive"))
      (node (ref "D022") (pin "A") (pinfunction "A_A") (pintype "passive"))
      (node (ref "D024") (pin "C") (pinfunction "C_C") (pintype "passive"))
      (node (ref "D035") (pin "A") (pinfunction "A_A") (pintype "passive"))
      (node (ref "D038") (pin "C") (pinfunction "C_C") (pintype "passive"))
      (node (ref "D047") (pin "A") (pinfunction "A_A") (pintype "passive"))
      (node (ref "D051") (pin "C") (pinfunction "C_C") (pintype "passive"))
      (node (ref "D058") (pin "A") (pinfunction "A_A") (pintype "passive"))
      (node (ref "D103") (pin "C") (pinfunction "C_C") (pintype "passive"))
      (node (ref "D108") (pin "A") (pinfunction "A_A") (pintype "passive"))
      (node (ref "D114") (pin "C") (pinfunction "C_C") (pintype "passive"))
      (node (ref "D117") (pin "A") (pinfunction "A_A") (pintype "passive"))
      (node (ref "D125") (pin "A") (pinfunction "A_A") (pintype "passive"))
      (node (ref "D132") (pin "A") (pinfunction "A_A") (pintype "passive"))
      (node (ref "J405") (pin "2") (pinfunction "2_2") (pintype "passive"))
      (node (ref "R3") (pin "7") (pinfunction "2_7") (pintype "passive"))
    )
    (net (code "36") (name "/Q11") (class "Default")
      (node (ref "D009") (pin "A") (pinfunction "A_A") (pintype "passive"))
      (node (ref "D010") (pin "C") (pinfunction "C_C") (pintype "passive"))
      (node (ref "D023") (pin "A") (pinfunction "A_A") (pintype "passive"))
      (node (ref "D025") (pin "C") (pinfunction "C_C") (pintype "passive"))
      (node (ref "D036") (pin "A") (pinfunction "A_A") (pintype "passive"))
      (node (ref "D039") (pin "C") (pinfunction "C_C") (pintype "passive"))
      (node (ref "D048") (pin "A") (pinfunction "A_A") (pintype "passive"))
      (node (ref "D052") (pin "C") (pinfunction "C_C") (pintype "passive"))
      (node (ref "D059") (pin "A") (pinfunction "A_A") (pintype "passive"))
      (node (ref "D104") (pin "C") (pinfunction "C_C") (pintype "passive"))
      (node (ref "D109") (pin "A") (pinfunction "A_A") (pintype "passive"))
      (node (ref "D118") (pin "A") (pinfunction "A_A") (pintype "passive"))
      (node (ref "D126") (pin "A") (pinfunction "A_A") (pintype "passive"))
      (node (ref "D133") (pin "A") (pinfunction "A_A") (pintype "passive"))
      (node (ref "D139") (pin "A") (pinfunction "A_A") (pintype "passive"))
      (node (ref "J405") (pin "3") (pinfunction "3_3") (pintype "passive"))
      (node (ref "R3") (pin "6") (pinfunction "2_6") (pintype "passive"))
    )
    (net (code "37") (name "/Q12") (class "Default")
      (node (ref "D010") (pin "A") (pinfunction "A_A") (pintype "passive"))
      (node (ref "D011") (pin "C") (pinfunction "C_C") (pintype "passive"))
      (node (ref "D024") (pin "A") (pinfunction "A_A") (pintype "passive"))
      (node (ref "D026") (pin "C") (pinfunction "C_C") (pintype "passive"))
      (node (ref "D037") (pin "A") (pinfunction "A_A") (pintype "passive"))
      (node (ref "D040") (pin "C") (pinfunction "C_C") (pintype "passive"))
      (node (ref "D049") (pin "A") (pinfunction "A_A") (pintype "passive"))
      (node (ref "D053") (pin "C") (pinfunction "C_C") (pintype "passive"))
      (node (ref "D100") (pin "A") (pinfunction "A_A") (pintype "passive"))
      (node (ref "D110") (pin "A") (pinfunction "A_A") (pintype "passive"))
      (node (ref "D119") (pin "A") (pinfunction "A_A") (pintype "passive"))
      (node (ref "D127") (pin "A") (pinfunction "A_A") (pintype "passive"))
      (node (ref "D134") (pin "A") (pinfunction "A_A") (pintype "passive"))
      (node (ref "D140") (pin "A") (pinfunction "A_A") (pintype "passive"))
      (node (ref "D145") (pin "A") (pinfunction "A_A") (pintype "passive"))
      (node (ref "J405") (pin "4") (pinfunction "4_4") (pintype "passive"))
      (node (ref "R3") (pin "5") (pinfunction "2_5") (pintype "passive"))
    )
    (net (code "38") (name "/Q13") (class "Default")
      (node (ref "D011") (pin "A") (pinfunction "A_A") (pintype "passive"))
      (node (ref "D012") (pin "C") (pinfunction "C_C") (pintype "passive"))
      (node (ref "D025") (pin "A") (pinfunction "A_A") (pintype "passive"))
      (node (ref "D027") (pin "C") (pinfunction "C_C") (pintype "passive"))
      (node (ref "D038") (pin "A") (pinfunction "A_A") (pintype "passive"))
      (node (ref "D041") (pin "C") (pinfunction "C_C") (pintype "passive"))
      (node (ref "D050") (pin "A") (pinfunction "A_A") (pintype "passive"))
      (node (ref "D101") (pin "A") (pinfunction "A_A") (pintype "passive"))
      (node (ref "D111") (pin "A") (pinfunction "A_A") (pintype "passive"))
      (node (ref "D120") (pin "A") (pinfunction "A_A") (pintype "passive"))
      (node (ref "D128") (pin "A") (pinfunction "A_A") (pintype "passive"))
      (node (ref "D135") (pin "A") (pinfunction "A_A") (pintype "passive"))
      (node (ref "D141") (pin "A") (pinfunction "A_A") (pintype "passive"))
      (node (ref "D146") (pin "A") (pinfunction "A_A") (pintype "passive"))
      (node (ref "D150") (pin "A") (pinfunction "A_A") (pintype "passive"))
      (node (ref "J405") (pin "5") (pinfunction "5_5") (pintype "passive"))
      (node (ref "R4") (pin "8") (pinfunction "2_8") (pintype "passive"))
    )
    (net (code "39") (name "/Q14") (class "Default")
      (node (ref "D012") (pin "A") (pinfunction "A_A") (pintype "passive"))
      (node (ref "D013") (pin "C") (pinfunction "C_C") (pintype "passive"))
      (node (ref "D026") (pin "A") (pinfunction "A_A") (pintype "passive"))
      (node (ref "D028") (pin "C") (pinfunction "C_C") (pintype "passive"))
      (node (ref "D039") (pin "A") (pinfunction "A_A") (pintype "passive"))
      (node (ref "D051") (pin "A") (pinfunction "A_A") (pintype "passive"))
      (node (ref "D102") (pin "A") (pinfunction "A_A") (pintype "passive"))
      (node (ref "D112") (pin "A") (pinfunction "A_A") (pintype "passive"))
      (node (ref "D121") (pin "A") (pinfunction "A_A") (pintype "passive"))
      (node (ref "D129") (pin "A") (pinfunction "A_A") (pintype "passive"))
      (node (ref "D136") (pin "A") (pinfunction "A_A") (pintype "passive"))
      (node (ref "D142") (pin "A") (pinfunction "A_A") (pintype "passive"))
      (node (ref "D147") (pin "A") (pinfunction "A_A") (pintype "passive"))
      (node (ref "D151") (pin "A") (pinfunction "A_A") (pintype "passive"))
      (node (ref "D154") (pin "A") (pinfunction "A_A") (pintype "passive"))
      (node (ref "J405") (pin "6") (pinfunction "6_6") (pintype "passive"))
      (node (ref "R4") (pin "7") (pinfunction "2_7") (pintype "passive"))
    )
    (net (code "40") (name "/Q15") (class "Default")
      (node (ref "D013") (pin "A") (pinfunction "A_A") (pintype "passive"))
      (node (ref "D014") (pin "C") (pinfunction "C_C") (pintype "passive"))
      (node (ref "D027") (pin "A") (pinfunction "A_A") (pintype "passive"))
      (node (ref "D040") (pin "A") (pinfunction "A_A") (pintype "passive"))
      (node (ref "D052") (pin "A") (pinfunction "A_A") (pintype "passive"))
      (node (ref "D103") (pin "A") (pinfunction "A_A") (pintype "passive"))
      (node (ref "D113") (pin "A") (pinfunction "A_A") (pintype "passive"))
      (node (ref "D122") (pin "A") (pinfunction "A_A") (pintype "passive"))
      (node (ref "D130") (pin "A") (pinfunction "A_A") (pintype "passive"))
      (node (ref "D137") (pin "A") (pinfunction "A_A") (pintype "passive"))
      (node (ref "D143") (pin "A") (pinfunction "A_A") (pintype "passive"))
      (node (ref "D148") (pin "A") (pinfunction "A_A") (pintype "passive"))
      (node (ref "D152") (pin "A") (pinfunction "A_A") (pintype "passive"))
      (node (ref "D155") (pin "A") (pinfunction "A_A") (pintype "passive"))
      (node (ref "D157") (pin "A") (pinfunction "A_A") (pintype "passive"))
      (node (ref "J405") (pin "7") (pinfunction "7_7") (pintype "passive"))
      (node (ref "R4") (pin "6") (pinfunction "2_6") (pintype "passive"))
    )
    (net (code "41") (name "/Q16") (class "Default")
      (node (ref "D014") (pin "A") (pinfunction "A_A") (pintype "passive"))
      (node (ref "D028") (pin "A") (pinfunction "A_A") (pintype "passive"))
      (node (ref "D041") (pin "A") (pinfunction "A_A") (pintype "passive"))
      (node (ref "D053") (pin "A") (pinfunction "A_A") (pintype "passive"))
      (node (ref "D104") (pin "A") (pinfunction "A_A") (pintype "passive"))
      (node (ref "D114") (pin "A") (pinfunction "A_A") (pintype "passive"))
      (node (ref "D123") (pin "A") (pinfunction "A_A") (pintype "passive"))
      (node (ref "D131") (pin "A") (pinfunction "A_A") (pintype "passive"))
      (node (ref "D138") (pin "A") (pinfunction "A_A") (pintype "passive"))
      (node (ref "D144") (pin "A") (pinfunction "A_A") (pintype "passive"))
      (node (ref "D149") (pin "A") (pinfunction "A_A") (pintype "passive"))
      (node (ref "D153") (pin "A") (pinfunction "A_A") (pintype "passive"))
      (node (ref "D156") (pin "A") (pinfunction "A_A") (pintype "passive"))
      (node (ref "D158") (pin "A") (pinfunction "A_A") (pintype "passive"))
      (node (ref "D159") (pin "A") (pinfunction "A_A") (pintype "passive"))
      (node (ref "J405") (pin "8") (pinfunction "8_8") (pintype "passive"))
      (node (ref "R4") (pin "5") (pinfunction "2_5") (pintype "passive"))
    )
    (net (code "42") (name "/RD+") (class "Default")
      (node (ref "R5") (pin "4") (pinfunction "2_4") (pintype "passive"))
      (node (ref "U401") (pin "4") (pinfunction "D+_4") (pintype "bidirectional"))
    )
    (net (code "43") (name "/RD-") (class "Default")
      (node (ref "R5") (pin "3") (pinfunction "2_3") (pintype "passive"))
      (node (ref "U401") (pin "3") (pinfunction "D-_3") (pintype "bidirectional"))
    )
    (net (code "44") (name "/RESET") (class "Default")
      (node (ref "J003") (pin "4") (pinfunction "4_4") (pintype "passive"))
      (node (ref "S429") (pin "P$2") (pinfunction "2_P$2") (pintype "bidirectional"))
      (node (ref "U401") (pin "13") (pinfunction "~{RESET}_13") (pintype "bidirectional"))
    )
    (net (code "45") (name "/RXLED") (class "Default")
      (node (ref "R501") (pin "2") (pinfunction "1_2") (pintype "passive"))
      (node (ref "U401") (pin "8") (pinfunction "PB0(SS)_8") (pintype "bidirectional"))
    )
    (net (code "46") (name "/SCK") (class "Default")
      (node (ref "J003") (pin "1") (pinfunction "1_1") (pintype "passive"))
      (node (ref "U401") (pin "9") (pinfunction "PB1(SCK)_9") (pintype "bidirectional"))
    )
    (net (code "47") (name "/TXLED") (class "Default")
      (node (ref "R501") (pin "1") (pinfunction "1_1") (pintype "passive"))
      (node (ref "U401") (pin "22") (pinfunction "PD5_22") (pintype "bidirectional"))
    )
    (net (code "48") (name "/UCAP") (class "Default")
      (node (ref "C406") (pin "1") (pinfunction "1_1") (pintype "passive"))
      (node (ref "U401") (pin "6") (pinfunction "UCAP_6") (pintype "bidirectional"))
    )
    (net (code "49") (name "/XTAL1") (class "Default")
      (node (ref "C417") (pin "2") (pinfunction "2_2") (pintype "passive"))
      (node (ref "U401") (pin "17") (pinfunction "XTAL1_17") (pintype "bidirectional"))
      (node (ref "Y401") (pin "1") (pinfunction "1_1") (pintype "passive"))
    )
    (net (code "50") (name "/XTAL2") (class "Default")
      (node (ref "C416") (pin "2") (pinfunction "2_2") (pintype "passive"))
      (node (ref "U401") (pin "16") (pinfunction "XTAL2_16") (pintype "bidirectional"))
      (node (ref "Y401") (pin "3") (pinfunction "2_3") (pintype "passive"))
    )
    (net (code "51") (name "GND") (class "Default")
      (node (ref "C010") (pin "2") (pinfunction "2_2") (pintype "passive"))
      (node (ref "C201") (pin "2") (pinfunction "2_2") (pintype "passive"))
      (node (ref "C203") (pin "2") (pinfunction "2_2") (pintype "passive"))
      (node (ref "C204") (pin "2") (pinfunction "2_2") (pintype "passive"))
      (node (ref "C406") (pin "2") (pinfunction "2_2") (pintype "passive"))
      (node (ref "C416") (pin "1") (pinfunction "1_1") (pintype "passive"))
      (node (ref "C417") (pin "1") (pinfunction "1_1") (pintype "passive"))
      (node (ref "J001") (pin "4") (pinfunction "4_4") (pintype "passive"))
      (node (ref "J002") (pin "4") (pinfunction "4_4") (pintype "passive"))
      (node (ref "J003") (pin "6") (pinfunction "6_6") (pintype "passive"))
      (node (ref "J004") (pin "3") (pinfunction "3_3") (pintype "passive"))
      (node (ref "R7") (pin "1") (pinfunction "1_1") (pintype "passive"))
      (node (ref "S429") (pin "P$1") (pinfunction "1_P$1") (pintype "bidirectional"))
      (node (ref "U201") (pin "2") (pinfunction "GND_2") (pintype "bidirectional"))
      (node (ref "U401") (pin "15") (pinfunction "GND_15") (pintype "bidirectional"))
      (node (ref "U401") (pin "23") (pinfunction "GND_23") (pintype "bidirectional"))
      (node (ref "U401") (pin "35") (pinfunction "GND_35") (pintype "bidirectional"))
      (node (ref "U401") (pin "43") (pinfunction "GND_43") (pintype "bidirectional"))
      (node (ref "U401") (pin "5") (pinfunction "UGND_5") (pintype "bidirectional"))
      (node (ref "Y401") (pin "2") (pinfunction "GND_2") (pintype "passive"))
      (node (ref "Y401") (pin "4") (pinfunction "GND_4") (pintype "passive"))
    )
    (net (code "52") (name "Net-(R501A-2)") (class "Default")
      (node (ref "D501") (pin "C") (pinfunction "C_C") (pintype "passive"))
      (node (ref "R501") (pin "4") (pinfunction "2_4") (pintype "passive"))
    )
    (net (code "53") (name "Net-(R501B-2)") (class "Default")
      (node (ref "D502") (pin "C") (pinfunction "C_C") (pintype "passive"))
      (node (ref "R501") (pin "3") (pinfunction "2_3") (pintype "passive"))
    )
    (net (code "54") (name "Net-(U201-BYP)") (class "Default")
      (node (ref "C203") (pin "1") (pinfunction "1_1") (pintype "passive"))
      (node (ref "U201") (pin "4") (pinfunction "BYP_4") (pintype "bidirectional"))
    )
    (net (code "55") (name "VCC") (class "Default")
      (node (ref "C010") (pin "1") (pinfunction "1_1") (pintype "passive"))
      (node (ref "C204") (pin "1") (pinfunction "1_1") (pintype "passive"))
      (node (ref "D501") (pin "A") (pinfunction "A_A") (pintype "passive"))
      (node (ref "D502") (pin "A") (pinfunction "A_A") (pintype "passive"))
      (node (ref "J001") (pin "3") (pinfunction "3_3") (pintype "passive"))
      (node (ref "J002") (pin "3") (pinfunction "3_3") (pintype "passive"))
      (node (ref "J003") (pin "5") (pinfunction "5_5") (pintype "passive"))
      (node (ref "U201") (pin "1") (pinfunction "VIN_1") (pintype "bidirectional"))
      (node (ref "U201") (pin "3") (pinfunction "EN_3") (pintype "bidirectional"))
      (node (ref "U401") (pin "14") (pinfunction "VCC_14") (pintype "bidirectional"))
      (node (ref "U401") (pin "2") (pinfunction "UVCC_2") (pintype "bidirectional"))
      (node (ref "U401") (pin "24") (pinfunction "AVCC_24") (pintype "bidirectional"))
      (node (ref "U401") (pin "34") (pinfunction "VCC_34") (pintype "bidirectional"))
      (node (ref "U401") (pin "42") (pinfunction "AREF_42") (pintype "bidirectional"))
      (node (ref "U401") (pin "44") (pinfunction "AVCC_44") (pintype "bidirectional"))
      (node (ref "U401") (pin "7") (pinfunction "VBUS_7") (pintype "bidirectional"))
    )
    (net (code "56") (name "unconnected-(U401-PD6(ADC9)-Pad26)") (class "Default")
      (node (ref "U401") (pin "26") (pinfunction "PD6(ADC9)_26") (pintype "bidirectional"))
    )
  )
)
